# SCH_DDM4351_EA_Circuit_Group_3_2022-05-2.net
KiCad netlist of a schematic drawn in EasyEDA
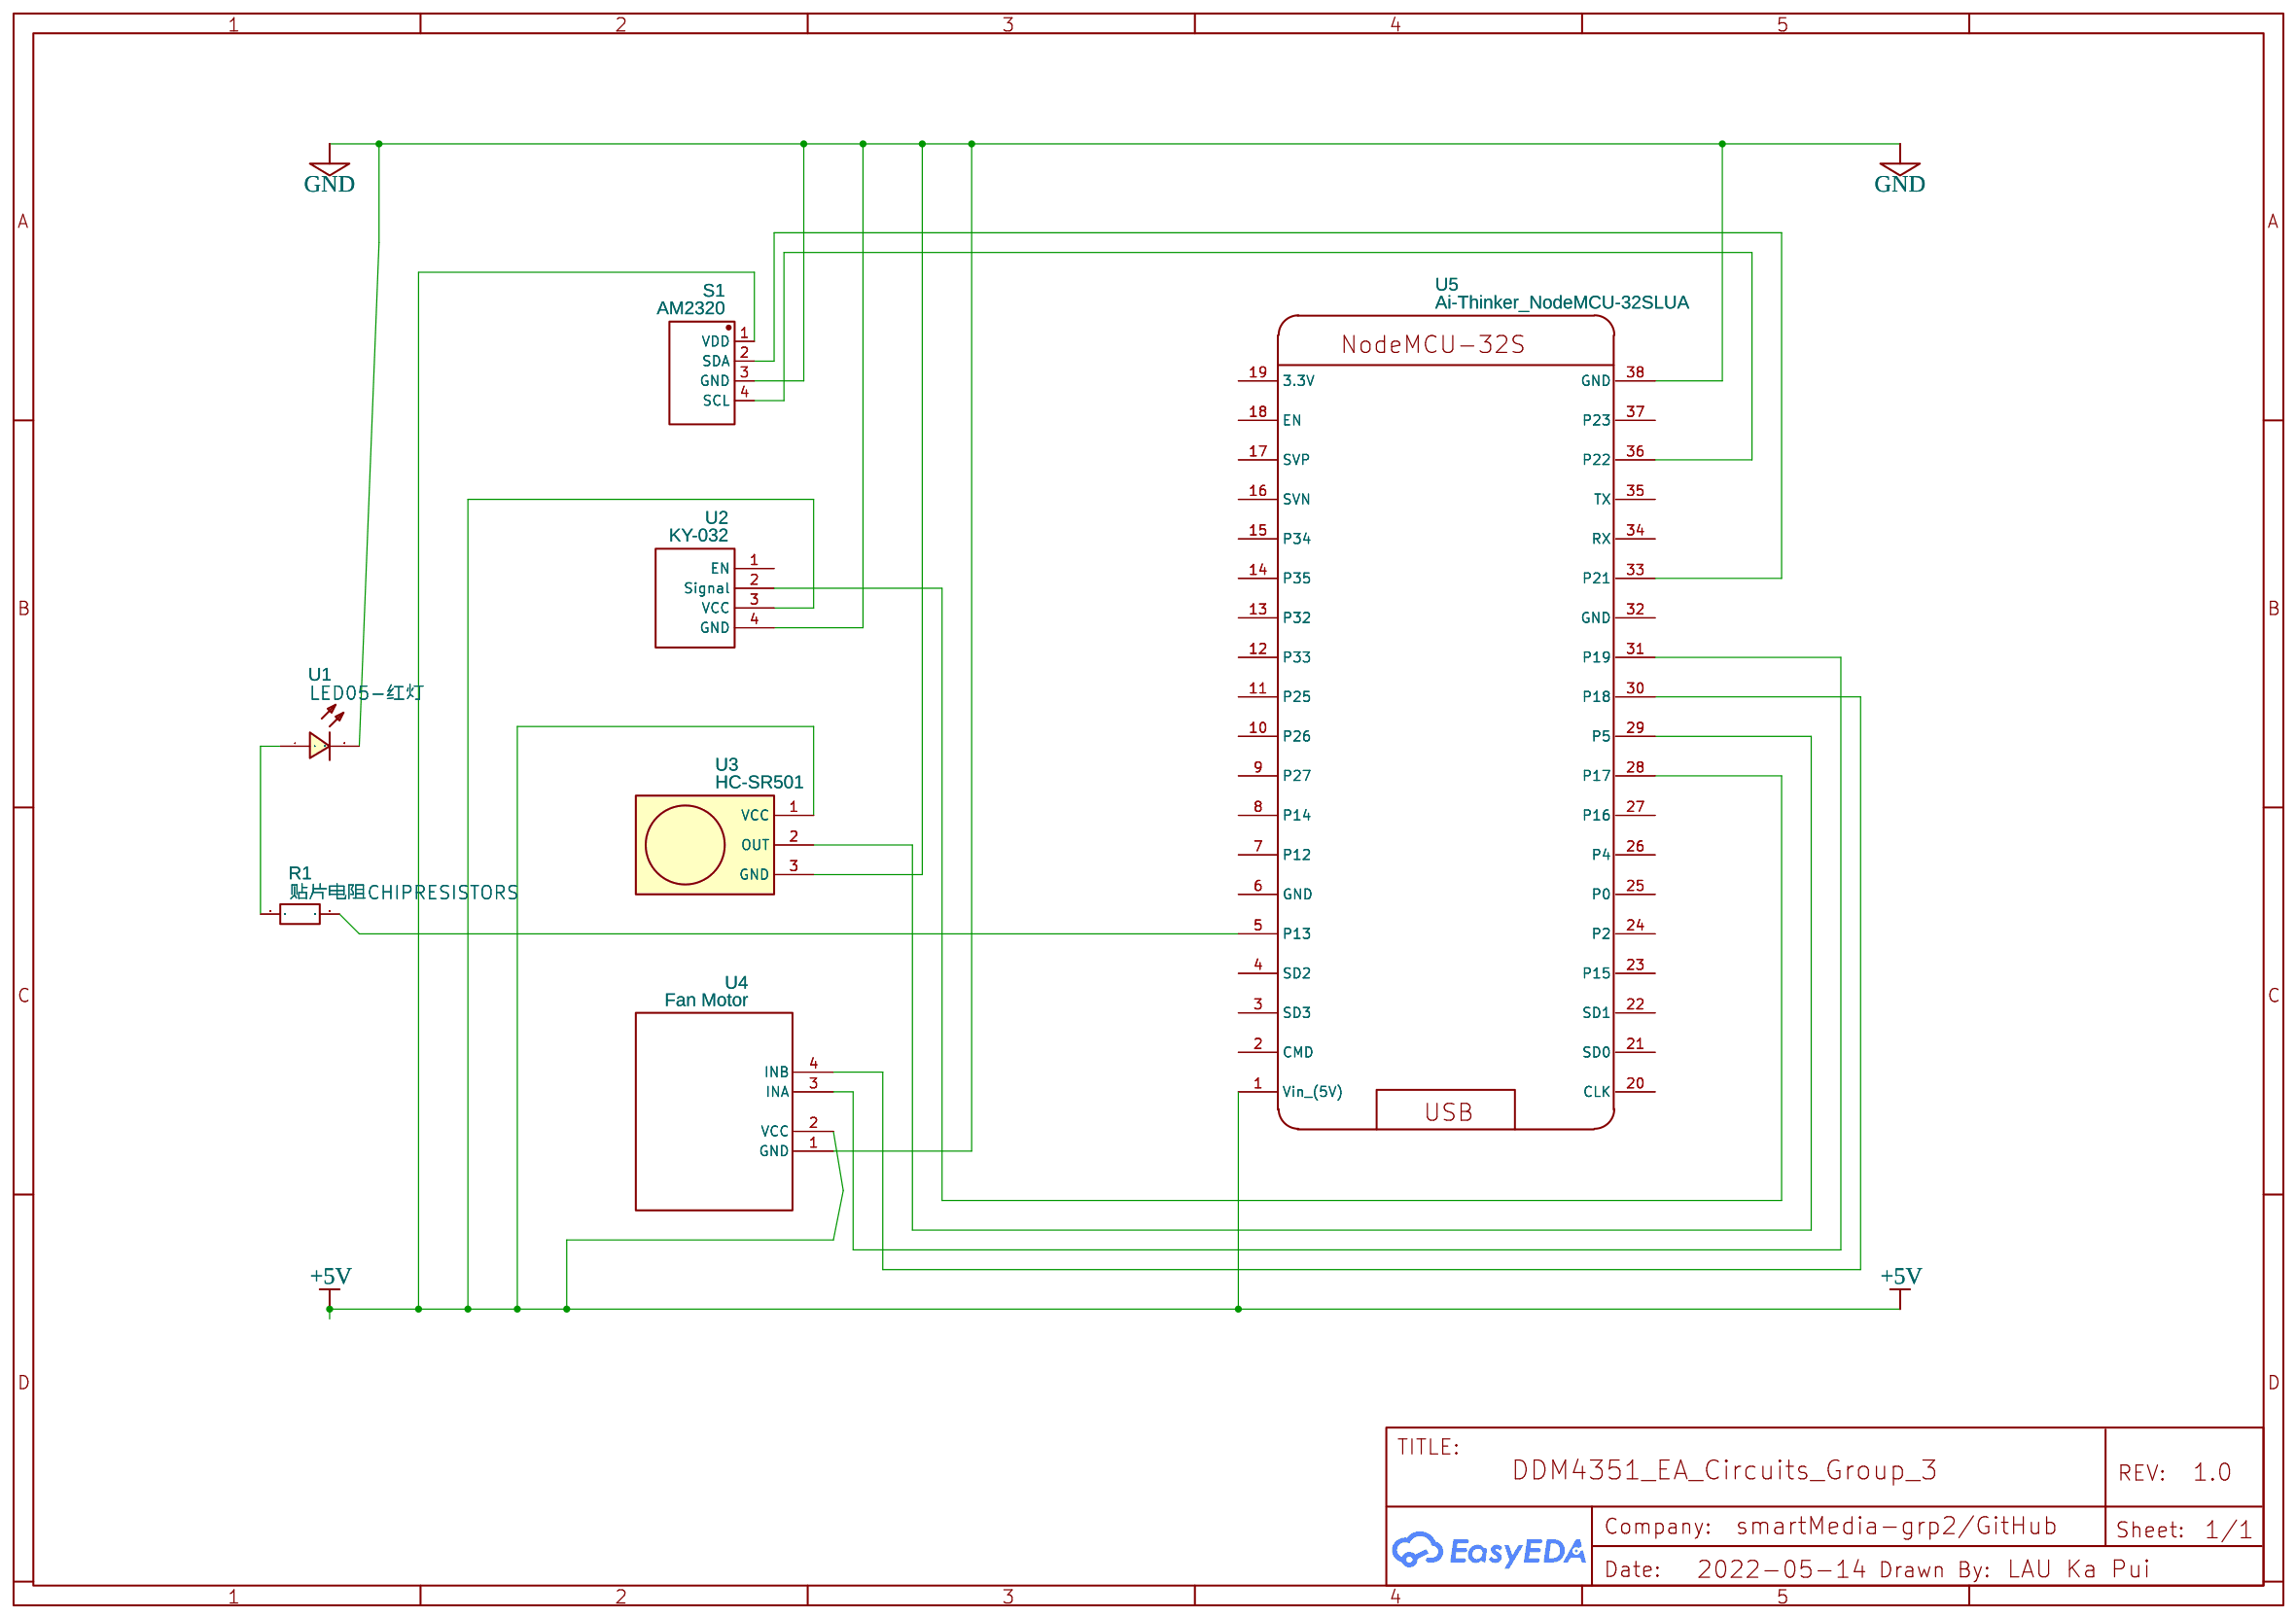
[diagram p0: schematic sheet]

(export (version "E")
  (design (tool "Eeschema 10.0.6"))
  (components
    (comp (ref "R1")
      (value "贴片电阻CHIPRESISTORS")
      (fields
        (field (name "BOM_Manufacturer Part") "贴片电阻ChipResistors")
        (field (name "BOM_Supplier Part") "C9900014833")
      )
      (libsource (lib "") (part "贴片电阻CHIPRESISTORS"))
    )
    (comp (ref "S1")
      (value "AM2320")
      (fields (field (name "BOM_Supplier Part") "C87932"))
      (libsource (lib "") (part "AM2320"))
    )
    (comp (ref "U1")
      (value "LED05-红灯")
      (fields (field (name "BOM_Supplier Part") "C9900009041"))
      (libsource (lib "") (part "LED05-红灯"))
    )
    (comp (ref "U2")
      (value "KY-032")
      (fields (field (name "BOM_Manufacturer Part") "Personal"))
      (libsource (lib "") (part "KY-032"))
    )
    (comp (ref "U3") (value "HC-SR501") (libsource (lib "") (part "HC-SR501")))
    (comp (ref "U4")
      (value "Fan Motor")
      (fields (field (name "BOM_Supplier Part") "undefined"))
      (libsource (lib "") (part "Grove - Vibration Motor"))
    )
    (comp (ref "U5")
      (value "Ai-Thinker_NodeMCU-32SLUA")
      (fields
        (field (name "BOM_Manufacturer Part") "NodeMCU-32SLua")
        (field (name "BOM_Supplier Part") "C111436")
      )
      (libsource (lib "") (part "Ai-Thinker_NodeMCU-32SLUA"))
    )
  )
  (nets
    (net (code "1") (name "+5V") (class "Default")
      (node (ref "S1") (pin "1") (pinfunction "VDD_1") (pintype "unspecified"))
      (node (ref "U2") (pin "3") (pinfunction "VCC_3") (pintype "unspecified"))
      (node (ref "U3") (pin "1") (pinfunction "VCC_1") (pintype "unspecified"))
      (node (ref "U4") (pin "2") (pinfunction "VCC_2") (pintype "unspecified"))
      (node (ref "U5") (pin "1") (pinfunction "Vin_(5V)_1") (pintype "unspecified"))
    )
    (net (code "2") (name "GND") (class "Default")
      (node (ref "S1") (pin "3") (pinfunction "GND_3") (pintype "unspecified"))
      (node (ref "U1") (pin "2") (pinfunction "2_2") (pintype "unspecified"))
      (node (ref "U2") (pin "4") (pinfunction "GND_4") (pintype "unspecified"))
      (node (ref "U3") (pin "3") (pinfunction "GND_3") (pintype "unspecified"))
      (node (ref "U4") (pin "1") (pinfunction "GND_1") (pintype "unspecified"))
      (node (ref "U5") (pin "38") (pinfunction "GND_38") (pintype "unspecified"))
    )
    (net (code "3") (name "Net-(R1-Pad1)") (class "Default")
      (node (ref "R1") (pin "1") (pinfunction "1_1") (pintype "unspecified"))
      (node (ref "U1") (pin "1") (pinfunction "1_1") (pintype "unspecified"))
    )
    (net (code "4") (name "Net-(S1-SCL)") (class "Default")
      (node (ref "S1") (pin "4") (pinfunction "SCL_4") (pintype "unspecified"))
      (node (ref "U5") (pin "36") (pinfunction "P22_36") (pintype "unspecified"))
    )
    (net (code "5") (name "Net-(S1-SDA)") (class "Default")
      (node (ref "S1") (pin "2") (pinfunction "SDA_2") (pintype "unspecified"))
      (node (ref "U5") (pin "33") (pinfunction "P21_33") (pintype "unspecified"))
    )
    (net (code "6") (name "Net-(U2-Signal)") (class "Default")
      (node (ref "U2") (pin "2") (pinfunction "Signal_2") (pintype "unspecified"))
      (node (ref "U5") (pin "28") (pinfunction "P17_28") (pintype "unspecified"))
    )
    (net (code "7") (name "Net-(U3-OUT)") (class "Default")
      (node (ref "U3") (pin "2") (pinfunction "OUT_2") (pintype "unspecified"))
      (node (ref "U5") (pin "29") (pinfunction "P5_29") (pintype "unspecified"))
    )
    (net (code "8") (name "Net-(U4-INA)") (class "Default")
      (node (ref "U4") (pin "3") (pinfunction "INA_3") (pintype "unspecified"))
      (node (ref "U5") (pin "31") (pinfunction "P19_31") (pintype "unspecified"))
    )
    (net (code "9") (name "Net-(U4-INB)") (class "Default")
      (node (ref "U4") (pin "4") (pinfunction "INB_4") (pintype "unspecified"))
      (node (ref "U5") (pin "30") (pinfunction "P18_30") (pintype "unspecified"))
    )
    (net (code "10") (name "Net-(U5-P13)") (class "Default")
      (node (ref "R1") (pin "2") (pinfunction "2_2") (pintype "unspecified"))
      (node (ref "U5") (pin "5") (pinfunction "P13_5") (pintype "unspecified"))
    )
    (net (code "11") (name "unconnected-(U2-EN-Pad1)") (class "Default")
      (node (ref "U2") (pin "1") (pinfunction "EN_1") (pintype "unspecified"))
    )
    (net (code "12") (name "unconnected-(U5-3.3V-Pad19)") (class "Default")
      (node (ref "U5") (pin "19") (pinfunction "3.3V_19") (pintype "unspecified"))
    )
    (net (code "13") (name "unconnected-(U5-CLK-Pad20)") (class "Default")
      (node (ref "U5") (pin "20") (pinfunction "CLK_20") (pintype "unspecified"))
    )
    (net (code "14") (name "unconnected-(U5-CMD-Pad2)") (class "Default")
      (node (ref "U5") (pin "2") (pinfunction "CMD_2") (pintype "unspecified"))
    )
    (net (code "15") (name "unconnected-(U5-EN-Pad18)") (class "Default")
      (node (ref "U5") (pin "18") (pinfunction "EN_18") (pintype "unspecified"))
    )
    (net (code "16") (name "unconnected-(U5-GND-Pad6)") (class "Default")
      (node (ref "U5") (pin "6") (pinfunction "GND_6") (pintype "unspecified"))
    )
    (net (code "17") (name "unconnected-(U5-GND-Pad32)") (class "Default")
      (node (ref "U5") (pin "32") (pinfunction "GND_32") (pintype "unspecified"))
    )
    (net (code "18") (name "unconnected-(U5-P0-Pad25)") (class "Default")
      (node (ref "U5") (pin "25") (pinfunction "P0_25") (pintype "unspecified"))
    )
    (net (code "19") (name "unconnected-(U5-P2-Pad24)") (class "Default")
      (node (ref "U5") (pin "24") (pinfunction "P2_24") (pintype "unspecified"))
    )
    (net (code "20") (name "unconnected-(U5-P4-Pad26)") (class "Default")
      (node (ref "U5") (pin "26") (pinfunction "P4_26") (pintype "unspecified"))
    )
    (net (code "21") (name "unconnected-(U5-P12-Pad7)") (class "Default")
      (node (ref "U5") (pin "7") (pinfunction "P12_7") (pintype "unspecified"))
    )
    (net (code "22") (name "unconnected-(U5-P14-Pad8)") (class "Default")
      (node (ref "U5") (pin "8") (pinfunction "P14_8") (pintype "unspecified"))
    )
    (net (code "23") (name "unconnected-(U5-P15-Pad23)") (class "Default")
      (node (ref "U5") (pin "23") (pinfunction "P15_23") (pintype "unspecified"))
    )
    (net (code "24") (name "unconnected-(U5-P16-Pad27)") (class "Default")
      (node (ref "U5") (pin "27") (pinfunction "P16_27") (pintype "unspecified"))
    )
    (net (code "25") (name "unconnected-(U5-P23-Pad37)") (class "Default")
      (node (ref "U5") (pin "37") (pinfunction "P23_37") (pintype "unspecified"))
    )
    (net (code "26") (name "unconnected-(U5-P25-Pad11)") (class "Default")
      (node (ref "U5") (pin "11") (pinfunction "P25_11") (pintype "unspecified"))
    )
    (net (code "27") (name "unconnected-(U5-P26-Pad10)") (class "Default")
      (node (ref "U5") (pin "10") (pinfunction "P26_10") (pintype "unspecified"))
    )
    (net (code "28") (name "unconnected-(U5-P27-Pad9)") (class "Default")
      (node (ref "U5") (pin "9") (pinfunction "P27_9") (pintype "unspecified"))
    )
    (net (code "29") (name "unconnected-(U5-P32-Pad13)") (class "Default")
      (node (ref "U5") (pin "13") (pinfunction "P32_13") (pintype "unspecified"))
    )
    (net (code "30") (name "unconnected-(U5-P33-Pad12)") (class "Default")
      (node (ref "U5") (pin "12") (pinfunction "P33_12") (pintype "unspecified"))
    )
    (net (code "31") (name "unconnected-(U5-P34-Pad15)") (class "Default")
      (node (ref "U5") (pin "15") (pinfunction "P34_15") (pintype "unspecified"))
    )
    (net (code "32") (name "unconnected-(U5-P35-Pad14)") (class "Default")
      (node (ref "U5") (pin "14") (pinfunction "P35_14") (pintype "unspecified"))
    )
    (net (code "33") (name "unconnected-(U5-RX-Pad34)") (class "Default")
      (node (ref "U5") (pin "34") (pinfunction "RX_34") (pintype "unspecified"))
    )
    (net (code "34") (name "unconnected-(U5-SD0-Pad21)") (class "Default")
      (node (ref "U5") (pin "21") (pinfunction "SD0_21") (pintype "unspecified"))
    )
    (net (code "35") (name "unconnected-(U5-SD1-Pad22)") (class "Default")
      (node (ref "U5") (pin "22") (pinfunction "SD1_22") (pintype "unspecified"))
    )
    (net (code "36") (name "unconnected-(U5-SD2-Pad4)") (class "Default")
      (node (ref "U5") (pin "4") (pinfunction "SD2_4") (pintype "unspecified"))
    )
    (net (code "37") (name "unconnected-(U5-SD3-Pad3)") (class "Default")
      (node (ref "U5") (pin "3") (pinfunction "SD3_3") (pintype "unspecified"))
    )
    (net (code "38") (name "unconnected-(U5-SVN-Pad16)") (class "Default")
      (node (ref "U5") (pin "16") (pinfunction "SVN_16") (pintype "unspecified"))
    )
    (net (code "39") (name "unconnected-(U5-SVP-Pad17)") (class "Default")
      (node (ref "U5") (pin "17") (pinfunction "SVP_17") (pintype "unspecified"))
    )
    (net (code "40") (name "unconnected-(U5-TX-Pad35)") (class "Default")
      (node (ref "U5") (pin "35") (pinfunction "TX_35") (pintype "unspecified"))
    )
  )
)
